# AMP2.net
KiCad netlist of a schematic drawn in Altium Designer
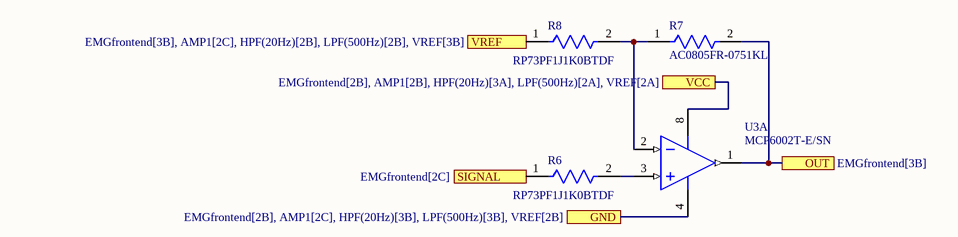
[diagram p0: AMP2.SchDoc]

(export (version "E")
  (design (tool "Eeschema 10.0.6"))
  (components
    (comp (ref "R6")
      (value "RP73PF1J1K0BTDF")
      (footprint "FP-RP73P-1J-MFG")
      (description "RP73P 0603 1KΩ 0.166W 25ppm/°C 0.10% 100V")
      (fields (field (name "TOLERANCE") "0.001"))
      (libsource (lib "Altium Content Vault") (part "1029c3af85768c4190bb7ad29bc67b5"))
    )
    (comp (ref "R7")
      (value "AC0805FR-0751KL")
      (footprint "FP-AC0805-MFG")
      (description "RES SMD 51K OHM 1% 1/8W 0805")
      (fields
        (field (name "MANUFACTURER") "Yageo")
        (field (name "OCTOPART") "https://octopart.com/ac0805fr-0751kl-yageo-24874955")
      )
      (libsource (lib "Altium Content Vault") (part "1029c3af85768c4190bb7ad29bc67b5"))
    )
    (comp (ref "R8")
      (value "RP73PF1J1K0BTDF")
      (footprint "FP-RP73P-1J-MFG")
      (description "RP73P 0603 1KΩ 0.166W 25ppm/°C 0.10% 100V")
      (fields (field (name "TOLERANCE") "0.001"))
      (libsource (lib "Altium Content Vault") (part "1029c3af85768c4190bb7ad29bc67b5"))
    )
    (comp (ref "U3")
      (value "MCP6002T-E/SN")
      (footprint "SOIC-SN8_N")
      (description "None")
      (libsource (lib "Altium Content Vault") (part "AMP-OPA-MCP6002-IL8"))
    )
  )
  (nets
    (net (code "1") (name "/GND") (class "Default")
      (node (ref "U3") (pin "4") (pinfunction "VSS_4") (pintype "power_in"))
    )
    (net (code "2") (name "/OUT") (class "Default")
      (node (ref "R7") (pin "2") (pinfunction "2_2") (pintype "passive"))
      (node (ref "U3") (pin "1") (pinfunction "VOUTA_1") (pintype "output"))
    )
    (net (code "3") (name "/SIGNAL") (class "Default")
      (node (ref "R6") (pin "1") (pinfunction "1_1") (pintype "passive"))
    )
    (net (code "4") (name "/VCC") (class "Default")
      (node (ref "U3") (pin "8") (pinfunction "VDD_8") (pintype "power_in"))
    )
    (net (code "5") (name "/VREF") (class "Default")
      (node (ref "R8") (pin "1") (pinfunction "1_1") (pintype "passive"))
    )
    (net (code "6") (name "Net-(U3A-VINA+)") (class "Default")
      (node (ref "R6") (pin "2") (pinfunction "2_2") (pintype "passive"))
      (node (ref "U3") (pin "3") (pinfunction "VINA+_3") (pintype "input"))
    )
    (net (code "7") (name "Net-(U3A-VINA-)") (class "Default")
      (node (ref "R7") (pin "1") (pinfunction "1_1") (pintype "passive"))
      (node (ref "R8") (pin "2") (pinfunction "2_2") (pintype "passive"))
      (node (ref "U3") (pin "2") (pinfunction "VINA-_2") (pintype "input"))
    )
  )
)
